# LED_Driver_and_Switches.net
KiCad netlist of a schematic drawn in Altium Designer
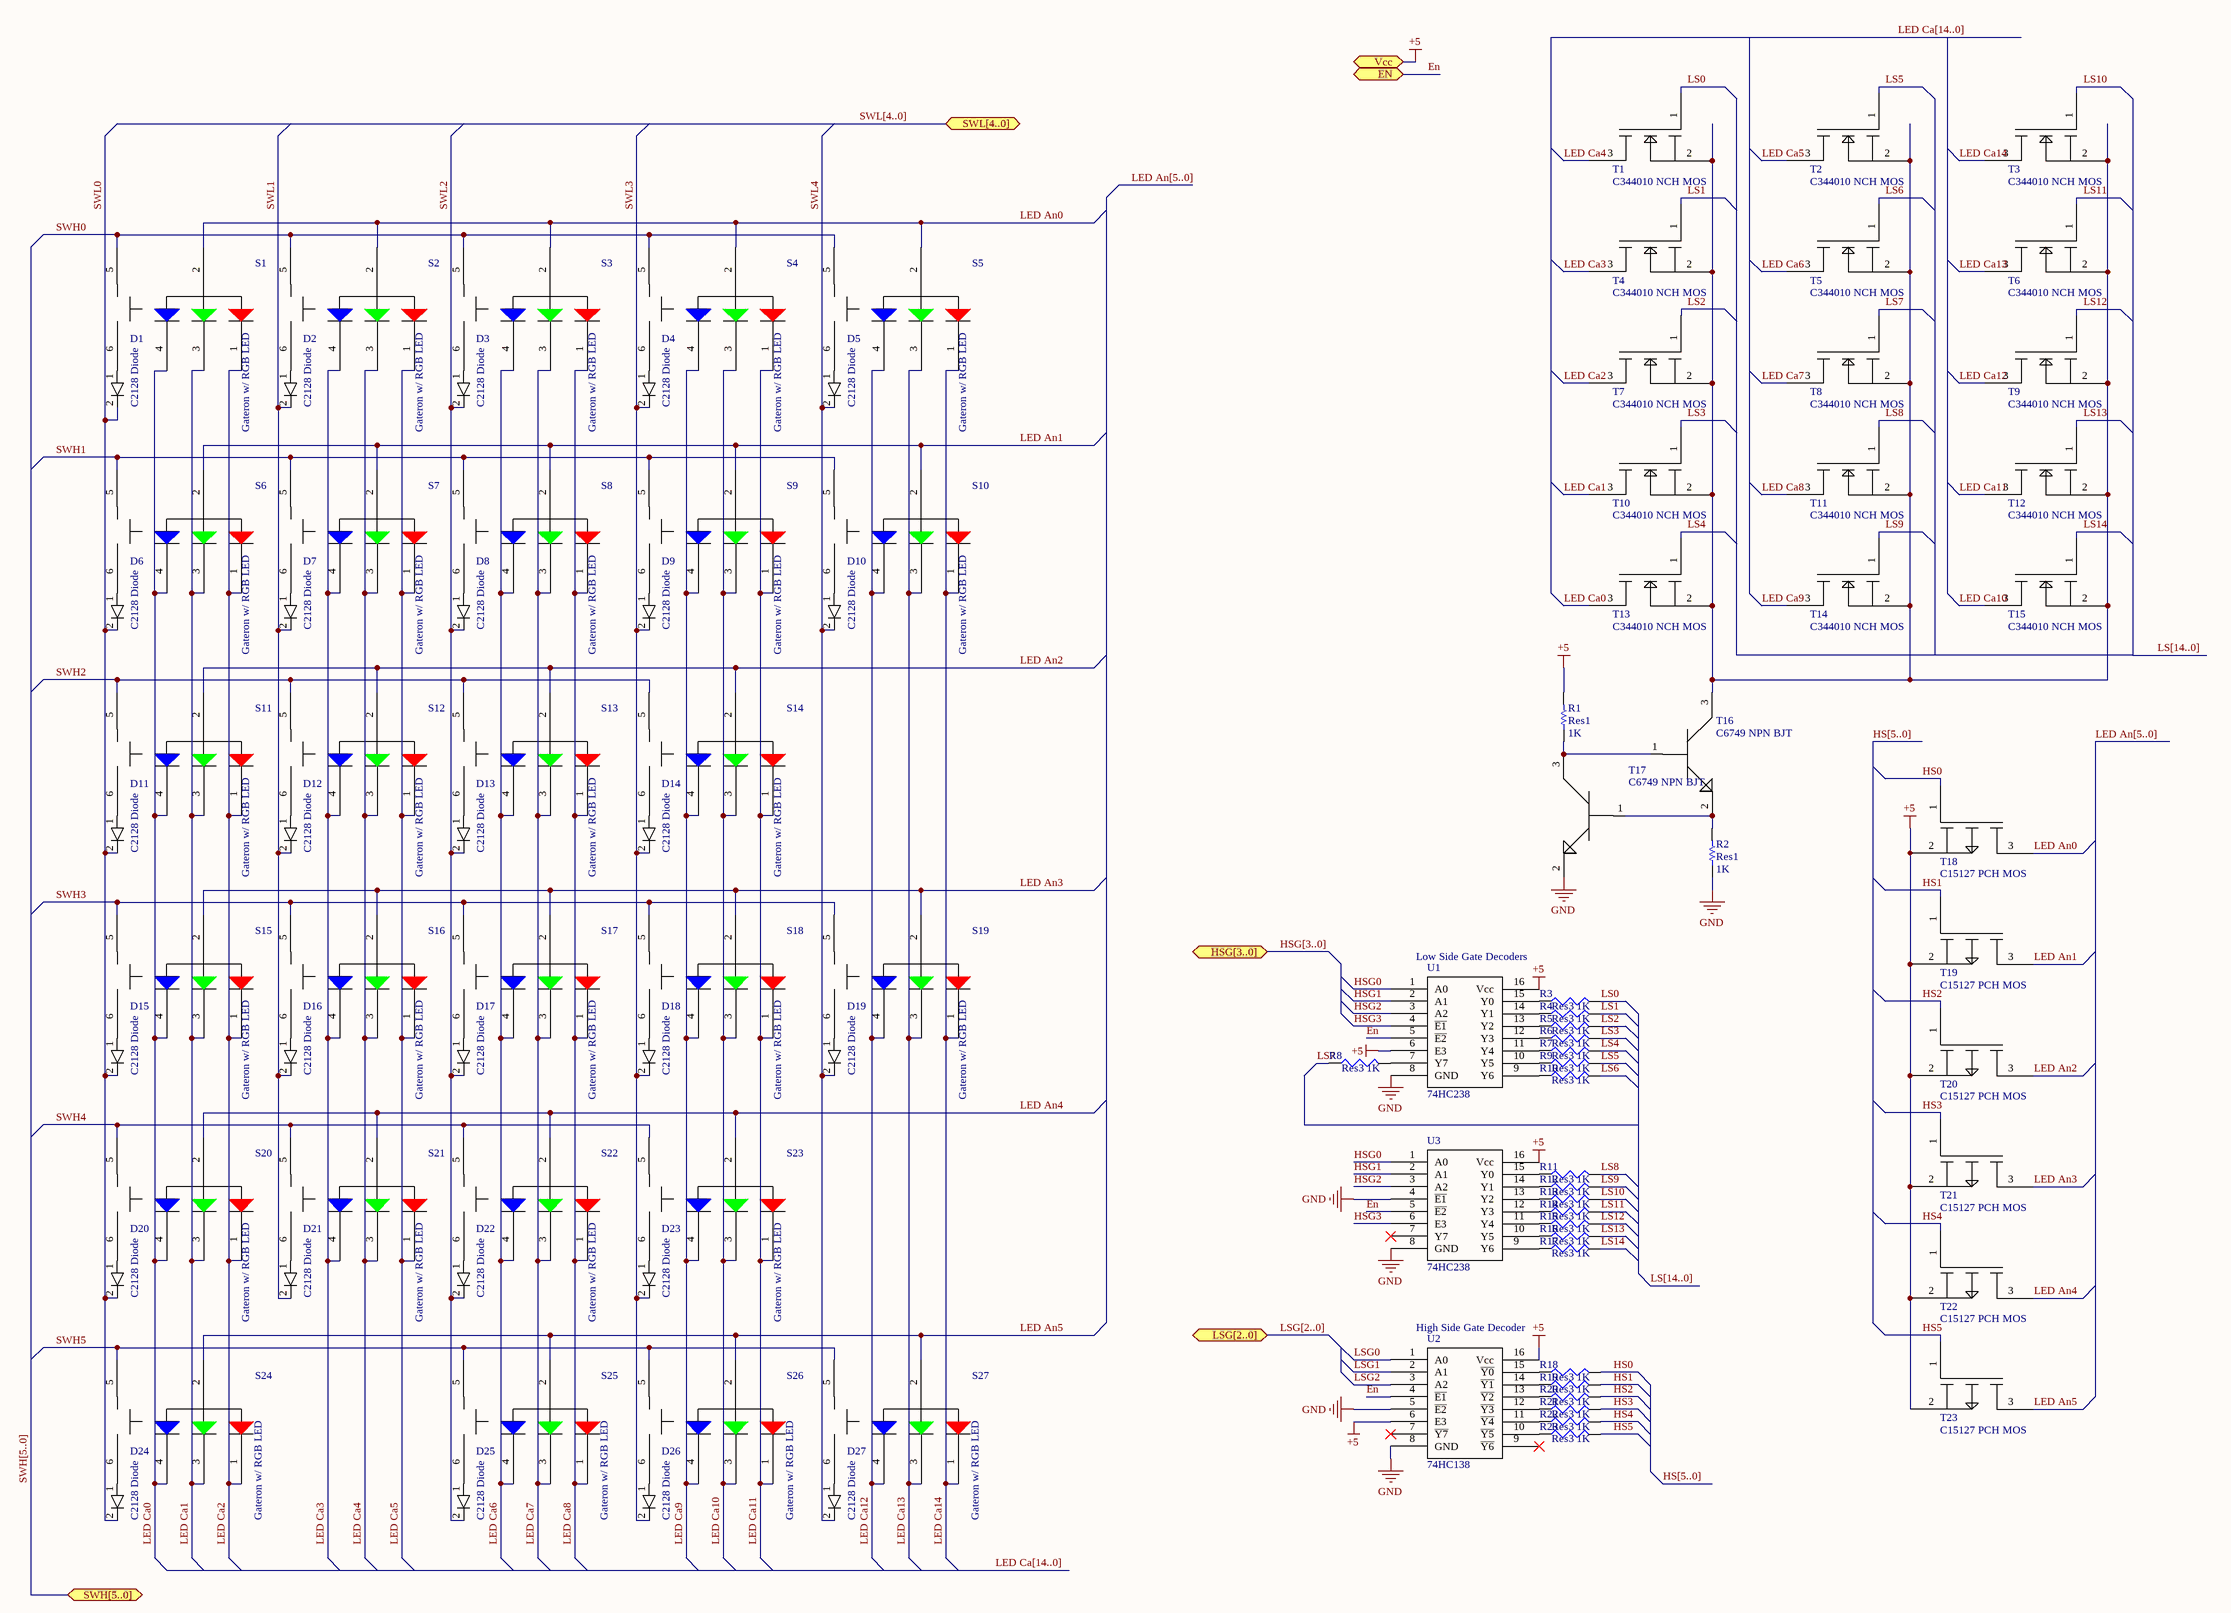
[diagram p0: LED Driver and Switches.SchDoc]

(export (version "E")
  (design (tool "Eeschema 10.0.6"))
  (components
    (comp (ref "D1")
      (value "C2128 Diode")
      (footprint "C2128 SOD323")
      (libsource (lib "2020-09-26_17-27-19") (part "C2128 Diode"))
    )
    (comp (ref "D2")
      (value "C2128 Diode")
      (footprint "C2128 SOD323")
      (libsource (lib "2020-09-26_17-27-19") (part "C2128 Diode"))
    )
    (comp (ref "D3")
      (value "C2128 Diode")
      (footprint "C2128 SOD323")
      (libsource (lib "2020-09-26_17-27-19") (part "C2128 Diode"))
    )
    (comp (ref "D4")
      (value "C2128 Diode")
      (footprint "C2128 SOD323")
      (libsource (lib "2020-09-26_17-27-19") (part "C2128 Diode"))
    )
    (comp (ref "D5")
      (value "C2128 Diode")
      (footprint "C2128 SOD323")
      (libsource (lib "2020-09-26_17-27-19") (part "C2128 Diode"))
    )
    (comp (ref "D6")
      (value "C2128 Diode")
      (footprint "C2128 SOD323")
      (libsource (lib "2020-09-26_17-27-19") (part "C2128 Diode"))
    )
    (comp (ref "D7")
      (value "C2128 Diode")
      (footprint "C2128 SOD323")
      (libsource (lib "2020-09-26_17-27-19") (part "C2128 Diode"))
    )
    (comp (ref "D8")
      (value "C2128 Diode")
      (footprint "C2128 SOD323")
      (libsource (lib "2020-09-26_17-27-19") (part "C2128 Diode"))
    )
    (comp (ref "D9")
      (value "C2128 Diode")
      (footprint "C2128 SOD323")
      (libsource (lib "2020-09-26_17-27-19") (part "C2128 Diode"))
    )
    (comp (ref "D10")
      (value "C2128 Diode")
      (footprint "C2128 SOD323")
      (libsource (lib "2020-09-26_17-27-19") (part "C2128 Diode"))
    )
    (comp (ref "D11")
      (value "C2128 Diode")
      (footprint "C2128 SOD323")
      (libsource (lib "2020-09-26_17-27-19") (part "C2128 Diode"))
    )
    (comp (ref "D12")
      (value "C2128 Diode")
      (footprint "C2128 SOD323")
      (libsource (lib "2020-09-26_17-27-19") (part "C2128 Diode"))
    )
    (comp (ref "D13")
      (value "C2128 Diode")
      (footprint "C2128 SOD323")
      (libsource (lib "2020-09-26_17-27-19") (part "C2128 Diode"))
    )
    (comp (ref "D14")
      (value "C2128 Diode")
      (footprint "C2128 SOD323")
      (libsource (lib "2020-09-26_17-27-19") (part "C2128 Diode"))
    )
    (comp (ref "D15")
      (value "C2128 Diode")
      (footprint "C2128 SOD323")
      (libsource (lib "2020-09-26_17-27-19") (part "C2128 Diode"))
    )
    (comp (ref "D16")
      (value "C2128 Diode")
      (footprint "C2128 SOD323")
      (libsource (lib "2020-09-26_17-27-19") (part "C2128 Diode"))
    )
    (comp (ref "D17")
      (value "C2128 Diode")
      (footprint "C2128 SOD323")
      (libsource (lib "2020-09-26_17-27-19") (part "C2128 Diode"))
    )
    (comp (ref "D18")
      (value "C2128 Diode")
      (footprint "C2128 SOD323")
      (libsource (lib "2020-09-26_17-27-19") (part "C2128 Diode"))
    )
    (comp (ref "D19")
      (value "C2128 Diode")
      (footprint "C2128 SOD323")
      (libsource (lib "2020-09-26_17-27-19") (part "C2128 Diode"))
    )
    (comp (ref "D20")
      (value "C2128 Diode")
      (footprint "C2128 SOD323")
      (libsource (lib "2020-09-26_17-27-19") (part "C2128 Diode"))
    )
    (comp (ref "D21")
      (value "C2128 Diode")
      (footprint "C2128 SOD323")
      (libsource (lib "2020-09-26_17-27-19") (part "C2128 Diode"))
    )
    (comp (ref "D22")
      (value "C2128 Diode")
      (footprint "C2128 SOD323")
      (libsource (lib "2020-09-26_17-27-19") (part "C2128 Diode"))
    )
    (comp (ref "D23")
      (value "C2128 Diode")
      (footprint "C2128 SOD323")
      (libsource (lib "2020-09-26_17-27-19") (part "C2128 Diode"))
    )
    (comp (ref "D24")
      (value "C2128 Diode")
      (footprint "C2128 SOD323")
      (libsource (lib "2020-09-26_17-27-19") (part "C2128 Diode"))
    )
    (comp (ref "D25")
      (value "C2128 Diode")
      (footprint "C2128 SOD323")
      (libsource (lib "2020-09-26_17-27-19") (part "C2128 Diode"))
    )
    (comp (ref "D26")
      (value "C2128 Diode")
      (footprint "C2128 SOD323")
      (libsource (lib "2020-09-26_17-27-19") (part "C2128 Diode"))
    )
    (comp (ref "D27")
      (value "C2128 Diode")
      (footprint "C2128 SOD323")
      (libsource (lib "2020-09-26_17-27-19") (part "C2128 Diode"))
    )
    (comp (ref "R1")
      (value "Res1")
      (footprint "AXIAL-0.3")
      (description "Resistor")
      (fields (field (name "ALTIUM_VALUE") "1K") (field (name "PUBLISHER") "Altium Limited"))
      (libsource (lib "Miscellaneous Devices") (part "Res1"))
    )
    (comp (ref "R2")
      (value "Res1")
      (footprint "AXIAL-0.3")
      (description "Resistor")
      (fields (field (name "ALTIUM_VALUE") "1K") (field (name "PUBLISHER") "Altium Limited"))
      (libsource (lib "Miscellaneous Devices") (part "Res1"))
    )
    (comp (ref "R3")
      (value "Res3")
      (footprint "J1-0603")
      (description "Resistor")
      (fields (field (name "ALTIUM_VALUE") "1K") (field (name "PUBLISHER") "Altium Limited"))
      (libsource (lib "Miscellaneous Devices") (part "Res3"))
    )
    (comp (ref "R4")
      (value "Res3")
      (footprint "J1-0603")
      (description "Resistor")
      (fields (field (name "ALTIUM_VALUE") "1K") (field (name "PUBLISHER") "Altium Limited"))
      (libsource (lib "Miscellaneous Devices") (part "Res3"))
    )
    (comp (ref "R5")
      (value "Res3")
      (footprint "J1-0603")
      (description "Resistor")
      (fields (field (name "ALTIUM_VALUE") "1K") (field (name "PUBLISHER") "Altium Limited"))
      (libsource (lib "Miscellaneous Devices") (part "Res3"))
    )
    (comp (ref "R6")
      (value "Res3")
      (footprint "J1-0603")
      (description "Resistor")
      (fields (field (name "ALTIUM_VALUE") "1K") (field (name "PUBLISHER") "Altium Limited"))
      (libsource (lib "Miscellaneous Devices") (part "Res3"))
    )
    (comp (ref "R7")
      (value "Res3")
      (footprint "J1-0603")
      (description "Resistor")
      (fields (field (name "ALTIUM_VALUE") "1K") (field (name "PUBLISHER") "Altium Limited"))
      (libsource (lib "Miscellaneous Devices") (part "Res3"))
    )
    (comp (ref "R8")
      (value "Res3")
      (footprint "J1-0603")
      (description "Resistor")
      (fields (field (name "ALTIUM_VALUE") "1K") (field (name "PUBLISHER") "Altium Limited"))
      (libsource (lib "Miscellaneous Devices") (part "Res3"))
    )
    (comp (ref "R9")
      (value "Res3")
      (footprint "J1-0603")
      (description "Resistor")
      (fields (field (name "ALTIUM_VALUE") "1K") (field (name "PUBLISHER") "Altium Limited"))
      (libsource (lib "Miscellaneous Devices") (part "Res3"))
    )
    (comp (ref "R10")
      (value "Res3")
      (footprint "J1-0603")
      (description "Resistor")
      (fields (field (name "ALTIUM_VALUE") "1K") (field (name "PUBLISHER") "Altium Limited"))
      (libsource (lib "Miscellaneous Devices") (part "Res3"))
    )
    (comp (ref "R11")
      (value "Res3")
      (footprint "J1-0603")
      (description "Resistor")
      (fields (field (name "ALTIUM_VALUE") "1K") (field (name "PUBLISHER") "Altium Limited"))
      (libsource (lib "Miscellaneous Devices") (part "Res3"))
    )
    (comp (ref "R12")
      (value "Res3")
      (footprint "J1-0603")
      (description "Resistor")
      (fields (field (name "ALTIUM_VALUE") "1K") (field (name "PUBLISHER") "Altium Limited"))
      (libsource (lib "Miscellaneous Devices") (part "Res3"))
    )
    (comp (ref "R13")
      (value "Res3")
      (footprint "J1-0603")
      (description "Resistor")
      (fields (field (name "ALTIUM_VALUE") "1K") (field (name "PUBLISHER") "Altium Limited"))
      (libsource (lib "Miscellaneous Devices") (part "Res3"))
    )
    (comp (ref "R14")
      (value "Res3")
      (footprint "J1-0603")
      (description "Resistor")
      (fields (field (name "ALTIUM_VALUE") "1K") (field (name "PUBLISHER") "Altium Limited"))
      (libsource (lib "Miscellaneous Devices") (part "Res3"))
    )
    (comp (ref "R15")
      (value "Res3")
      (footprint "J1-0603")
      (description "Resistor")
      (fields (field (name "ALTIUM_VALUE") "1K") (field (name "PUBLISHER") "Altium Limited"))
      (libsource (lib "Miscellaneous Devices") (part "Res3"))
    )
    (comp (ref "R16")
      (value "Res3")
      (footprint "J1-0603")
      (description "Resistor")
      (fields (field (name "ALTIUM_VALUE") "1K") (field (name "PUBLISHER") "Altium Limited"))
      (libsource (lib "Miscellaneous Devices") (part "Res3"))
    )
    (comp (ref "R17")
      (value "Res3")
      (footprint "J1-0603")
      (description "Resistor")
      (fields (field (name "ALTIUM_VALUE") "1K") (field (name "PUBLISHER") "Altium Limited"))
      (libsource (lib "Miscellaneous Devices") (part "Res3"))
    )
    (comp (ref "R18")
      (value "Res3")
      (footprint "J1-0603")
      (description "Resistor")
      (fields (field (name "ALTIUM_VALUE") "1K") (field (name "PUBLISHER") "Altium Limited"))
      (libsource (lib "Miscellaneous Devices") (part "Res3"))
    )
    (comp (ref "R19")
      (value "Res3")
      (footprint "J1-0603")
      (description "Resistor")
      (fields (field (name "ALTIUM_VALUE") "1K") (field (name "PUBLISHER") "Altium Limited"))
      (libsource (lib "Miscellaneous Devices") (part "Res3"))
    )
    (comp (ref "R20")
      (value "Res3")
      (footprint "J1-0603")
      (description "Resistor")
      (fields (field (name "ALTIUM_VALUE") "1K") (field (name "PUBLISHER") "Altium Limited"))
      (libsource (lib "Miscellaneous Devices") (part "Res3"))
    )
    (comp (ref "R21")
      (value "Res3")
      (footprint "J1-0603")
      (description "Resistor")
      (fields (field (name "ALTIUM_VALUE") "1K") (field (name "PUBLISHER") "Altium Limited"))
      (libsource (lib "Miscellaneous Devices") (part "Res3"))
    )
    (comp (ref "R22")
      (value "Res3")
      (footprint "J1-0603")
      (description "Resistor")
      (fields (field (name "ALTIUM_VALUE") "1K") (field (name "PUBLISHER") "Altium Limited"))
      (libsource (lib "Miscellaneous Devices") (part "Res3"))
    )
    (comp (ref "R23")
      (value "Res3")
      (footprint "J1-0603")
      (description "Resistor")
      (fields (field (name "ALTIUM_VALUE") "1K") (field (name "PUBLISHER") "Altium Limited"))
      (libsource (lib "Miscellaneous Devices") (part "Res3"))
    )
    (comp (ref "S1")
      (value "Gateron w/ RGB LED")
      (footprint "Gateron Green")
      (libsource (lib "2020-09-26_17-27-19") (part "Gateron Green"))
    )
    (comp (ref "S2")
      (value "Gateron w/ RGB LED")
      (footprint "Gateron Green")
      (libsource (lib "2020-09-26_17-27-19") (part "Gateron Green"))
    )
    (comp (ref "S3")
      (value "Gateron w/ RGB LED")
      (footprint "Gateron Green")
      (libsource (lib "2020-09-26_17-27-19") (part "Gateron Green"))
    )
    (comp (ref "S4")
      (value "Gateron w/ RGB LED")
      (footprint "Gateron Green")
      (libsource (lib "2020-09-26_17-27-19") (part "Gateron Green"))
    )
    (comp (ref "S5")
      (value "Gateron w/ RGB LED")
      (footprint "Gateron Green")
      (libsource (lib "2020-09-26_17-27-19") (part "Gateron Green"))
    )
    (comp (ref "S6")
      (value "Gateron w/ RGB LED")
      (footprint "Gateron Green")
      (libsource (lib "2020-09-26_17-27-19") (part "Gateron Green"))
    )
    (comp (ref "S7")
      (value "Gateron w/ RGB LED")
      (footprint "Gateron Green")
      (libsource (lib "2020-09-26_17-27-19") (part "Gateron Green"))
    )
    (comp (ref "S8")
      (value "Gateron w/ RGB LED")
      (footprint "Gateron Green")
      (libsource (lib "2020-09-26_17-27-19") (part "Gateron Green"))
    )
    (comp (ref "S9")
      (value "Gateron w/ RGB LED")
      (footprint "Gateron Green")
      (libsource (lib "2020-09-26_17-27-19") (part "Gateron Green"))
    )
    (comp (ref "S10")
      (value "Gateron w/ RGB LED")
      (footprint "Gateron Green")
      (libsource (lib "2020-09-26_17-27-19") (part "Gateron Green"))
    )
    (comp (ref "S11")
      (value "Gateron w/ RGB LED")
      (footprint "Gateron Green")
      (libsource (lib "2020-09-26_17-27-19") (part "Gateron Green"))
    )
    (comp (ref "S12")
      (value "Gateron w/ RGB LED")
      (footprint "Gateron Green")
      (libsource (lib "2020-09-26_17-27-19") (part "Gateron Green"))
    )
    (comp (ref "S13")
      (value "Gateron w/ RGB LED")
      (footprint "Gateron Green")
      (libsource (lib "2020-09-26_17-27-19") (part "Gateron Green"))
    )
    (comp (ref "S14")
      (value "Gateron w/ RGB LED")
      (footprint "Gateron Green")
      (libsource (lib "2020-09-26_17-27-19") (part "Gateron Green"))
    )
    (comp (ref "S15")
      (value "Gateron w/ RGB LED")
      (footprint "Gateron Green")
      (libsource (lib "2020-09-26_17-27-19") (part "Gateron Green"))
    )
    (comp (ref "S16")
      (value "Gateron w/ RGB LED")
      (footprint "Gateron Green")
      (libsource (lib "2020-09-26_17-27-19") (part "Gateron Green"))
    )
    (comp (ref "S17")
      (value "Gateron w/ RGB LED")
      (footprint "Gateron Green")
      (libsource (lib "2020-09-26_17-27-19") (part "Gateron Green"))
    )
    (comp (ref "S18")
      (value "Gateron w/ RGB LED")
      (footprint "Gateron Green")
      (libsource (lib "2020-09-26_17-27-19") (part "Gateron Green"))
    )
    (comp (ref "S19")
      (value "Gateron w/ RGB LED")
      (footprint "Gateron Green")
      (libsource (lib "2020-09-26_17-27-19") (part "Gateron Green"))
    )
    (comp (ref "S20")
      (value "Gateron w/ RGB LED")
      (footprint "Gateron Green")
      (libsource (lib "2020-09-26_17-27-19") (part "Gateron Green"))
    )
    (comp (ref "S21")
      (value "Gateron w/ RGB LED")
      (footprint "Gateron Green")
      (libsource (lib "2020-09-26_17-27-19") (part "Gateron Green"))
    )
    (comp (ref "S22")
      (value "Gateron w/ RGB LED")
      (footprint "Gateron Green")
      (libsource (lib "2020-09-26_17-27-19") (part "Gateron Green"))
    )
    (comp (ref "S23")
      (value "Gateron w/ RGB LED")
      (footprint "Gateron Green")
      (libsource (lib "2020-09-26_17-27-19") (part "Gateron Green"))
    )
    (comp (ref "S24")
      (value "Gateron w/ RGB LED")
      (footprint "Gateron Green")
      (libsource (lib "2020-09-26_17-27-19") (part "Gateron Green"))
    )
    (comp (ref "S25")
      (value "Gateron w/ RGB LED")
      (footprint "Gateron Green")
      (libsource (lib "2020-09-26_17-27-19") (part "Gateron Green"))
    )
    (comp (ref "S26")
      (value "Gateron w/ RGB LED")
      (footprint "Gateron Green")
      (libsource (lib "2020-09-26_17-27-19") (part "Gateron Green"))
    )
    (comp (ref "S27")
      (value "Gateron w/ RGB LED")
      (footprint "Gateron Green")
      (libsource (lib "2020-09-26_17-27-19") (part "Gateron Green"))
    )
    (comp (ref "T1")
      (value "C344010 NCH MOS")
      (footprint "C6749 NPN BJT")
      (libsource (lib "2020-09-26_17-27-19") (part "C344010 NCH MOS"))
    )
    (comp (ref "T2")
      (value "C344010 NCH MOS")
      (footprint "C6749 NPN BJT")
      (libsource (lib "2020-09-26_17-27-19") (part "C344010 NCH MOS"))
    )
    (comp (ref "T3")
      (value "C344010 NCH MOS")
      (footprint "C6749 NPN BJT")
      (libsource (lib "2020-09-26_17-27-19") (part "C344010 NCH MOS"))
    )
    (comp (ref "T4")
      (value "C344010 NCH MOS")
      (footprint "C6749 NPN BJT")
      (libsource (lib "2020-09-26_17-27-19") (part "C344010 NCH MOS"))
    )
    (comp (ref "T5")
      (value "C344010 NCH MOS")
      (footprint "C6749 NPN BJT")
      (libsource (lib "2020-09-26_17-27-19") (part "C344010 NCH MOS"))
    )
    (comp (ref "T6")
      (value "C344010 NCH MOS")
      (footprint "C6749 NPN BJT")
      (libsource (lib "2020-09-26_17-27-19") (part "C344010 NCH MOS"))
    )
    (comp (ref "T7")
      (value "C344010 NCH MOS")
      (footprint "C6749 NPN BJT")
      (libsource (lib "2020-09-26_17-27-19") (part "C344010 NCH MOS"))
    )
    (comp (ref "T8")
      (value "C344010 NCH MOS")
      (footprint "C6749 NPN BJT")
      (libsource (lib "2020-09-26_17-27-19") (part "C344010 NCH MOS"))
    )
    (comp (ref "T9")
      (value "C344010 NCH MOS")
      (footprint "C6749 NPN BJT")
      (libsource (lib "2020-09-26_17-27-19") (part "C344010 NCH MOS"))
    )
    (comp (ref "T10")
      (value "C344010 NCH MOS")
      (footprint "C6749 NPN BJT")
      (libsource (lib "2020-09-26_17-27-19") (part "C344010 NCH MOS"))
    )
    (comp (ref "T11")
      (value "C344010 NCH MOS")
      (footprint "C6749 NPN BJT")
      (libsource (lib "2020-09-26_17-27-19") (part "C344010 NCH MOS"))
    )
    (comp (ref "T12")
      (value "C344010 NCH MOS")
      (footprint "C6749 NPN BJT")
      (libsource (lib "2020-09-26_17-27-19") (part "C344010 NCH MOS"))
    )
    (comp (ref "T13")
      (value "C344010 NCH MOS")
      (footprint "C6749 NPN BJT")
      (libsource (lib "2020-09-26_17-27-19") (part "C344010 NCH MOS"))
    )
    (comp (ref "T14")
      (value "C344010 NCH MOS")
      (footprint "C6749 NPN BJT")
      (libsource (lib "2020-09-26_17-27-19") (part "C344010 NCH MOS"))
    )
    (comp (ref "T15")
      (value "C344010 NCH MOS")
      (footprint "C6749 NPN BJT")
      (libsource (lib "2020-09-26_17-27-19") (part "C344010 NCH MOS"))
    )
    (comp (ref "T16")
      (value "C6749 NPN BJT")
      (footprint "C6749 NPN BJT")
      (libsource (lib "2020-09-26_17-27-19") (part "C6749 NPN BJT"))
    )
    (comp (ref "T17")
      (value "C6749 NPN BJT")
      (footprint "C6749 NPN BJT")
      (libsource (lib "2020-09-26_17-27-19") (part "C6749 NPN BJT"))
    )
    (comp (ref "T18")
      (value "C15127 PCH MOS")
      (footprint "C6749 NPN BJT")
      (libsource (lib "2020-09-26_17-27-19") (part "C15127 PCH MOS"))
    )
    (comp (ref "T19")
      (value "C15127 PCH MOS")
      (footprint "C6749 NPN BJT")
      (libsource (lib "2020-09-26_17-27-19") (part "C15127 PCH MOS"))
    )
    (comp (ref "T20")
      (value "C15127 PCH MOS")
      (footprint "C6749 NPN BJT")
      (libsource (lib "2020-09-26_17-27-19") (part "C15127 PCH MOS"))
    )
    (comp (ref "T21")
      (value "C15127 PCH MOS")
      (footprint "C6749 NPN BJT")
      (libsource (lib "2020-09-26_17-27-19") (part "C15127 PCH MOS"))
    )
    (comp (ref "T22")
      (value "C15127 PCH MOS")
      (footprint "C6749 NPN BJT")
      (libsource (lib "2020-09-26_17-27-19") (part "C15127 PCH MOS"))
    )
    (comp (ref "T23")
      (value "C15127 PCH MOS")
      (footprint "C6749 NPN BJT")
      (libsource (lib "2020-09-26_17-27-19") (part "C15127 PCH MOS"))
    )
    (comp (ref "U1")
      (value "74HC238")
      (footprint "SOIC16")
      (libsource (lib "2020-09-26_17-27-19") (part "74HC238"))
    )
    (comp (ref "U2")
      (value "74HC138")
      (footprint "SOIC16")
      (libsource (lib "2020-09-26_17-27-19") (part "74HC138"))
    )
    (comp (ref "U3")
      (value "74HC238")
      (footprint "SOIC16")
      (libsource (lib "2020-09-26_17-27-19") (part "74HC238"))
    )
  )
  (nets
    (net (code "1") (name "+5") (class "Default")
      (node (ref "R1") (pin "2") (pinfunction "2_2") (pintype "passive"))
      (node (ref "T18") (pin "2") (pintype "passive"))
      (node (ref "T19") (pin "2") (pintype "passive"))
      (node (ref "T20") (pin "2") (pintype "passive"))
      (node (ref "T21") (pin "2") (pintype "passive"))
      (node (ref "T22") (pin "2") (pintype "passive"))
      (node (ref "T23") (pin "2") (pintype "passive"))
      (node (ref "U1") (pin "16") (pinfunction "Vcc_16") (pintype "passive"))
      (node (ref "U1") (pin "6") (pinfunction "E3_6") (pintype "passive"))
      (node (ref "U2") (pin "16") (pinfunction "Vcc_16") (pintype "passive"))
      (node (ref "U2") (pin "6") (pinfunction "E3_6") (pintype "passive"))
      (node (ref "U3") (pin "16") (pinfunction "Vcc_16") (pintype "passive"))
    )
    (net (code "2") (name "/En") (class "Default")
      (node (ref "U1") (pin "5") (pinfunction "~{E2}_5") (pintype "passive"))
      (node (ref "U2") (pin "4") (pinfunction "~{E1}_4") (pintype "passive"))
      (node (ref "U3") (pin "5") (pinfunction "~{E2}_5") (pintype "passive"))
    )
    (net (code "3") (name "/HS0") (class "Default")
      (node (ref "R18") (pin "2") (pinfunction "2_2") (pintype "passive"))
      (node (ref "T18") (pin "1") (pintype "passive"))
    )
    (net (code "4") (name "/HS1") (class "Default")
      (node (ref "R19") (pin "2") (pinfunction "2_2") (pintype "passive"))
      (node (ref "T19") (pin "1") (pintype "passive"))
    )
    (net (code "5") (name "/HS2") (class "Default")
      (node (ref "R20") (pin "2") (pinfunction "2_2") (pintype "passive"))
      (node (ref "T20") (pin "1") (pintype "passive"))
    )
    (net (code "6") (name "/HS3") (class "Default")
      (node (ref "R21") (pin "2") (pinfunction "2_2") (pintype "passive"))
      (node (ref "T21") (pin "1") (pintype "passive"))
    )
    (net (code "7") (name "/HS4") (class "Default")
      (node (ref "R22") (pin "2") (pinfunction "2_2") (pintype "passive"))
      (node (ref "T22") (pin "1") (pintype "passive"))
    )
    (net (code "8") (name "/HS5") (class "Default")
      (node (ref "R23") (pin "2") (pinfunction "2_2") (pintype "passive"))
      (node (ref "T23") (pin "1") (pintype "passive"))
    )
    (net (code "9") (name "/HSG0") (class "Default")
      (node (ref "U1") (pin "1") (pinfunction "A0_1") (pintype "passive"))
      (node (ref "U3") (pin "1") (pinfunction "A0_1") (pintype "passive"))
    )
    (net (code "10") (name "/HSG1") (class "Default")
      (node (ref "U1") (pin "2") (pinfunction "A1_2") (pintype "passive"))
      (node (ref "U3") (pin "2") (pinfunction "A1_2") (pintype "passive"))
    )
    (net (code "11") (name "/HSG2") (class "Default")
      (node (ref "U1") (pin "3") (pinfunction "A2_3") (pintype "passive"))
      (node (ref "U3") (pin "3") (pinfunction "A2_3") (pintype "passive"))
    )
    (net (code "12") (name "/HSG3") (class "Default")
      (node (ref "U1") (pin "4") (pinfunction "~{E1}_4") (pintype "passive"))
      (node (ref "U3") (pin "6") (pinfunction "E3_6") (pintype "passive"))
    )
    (net (code "15") (name "/LED An0") (class "Default")
      (node (ref "S1") (pin "2") (pinfunction "COM_2") (pintype "passive"))
      (node (ref "S2") (pin "2") (pinfunction "COM_2") (pintype "passive"))
      (node (ref "S3") (pin "2") (pinfunction "COM_2") (pintype "passive"))
      (node (ref "S4") (pin "2") (pinfunction "COM_2") (pintype "passive"))
      (node (ref "S5") (pin "2") (pinfunction "COM_2") (pintype "passive"))
      (node (ref "T18") (pin "3") (pintype "passive"))
    )
    (net (code "16") (name "/LED An1") (class "Default")
      (node (ref "S10") (pin "2") (pinfunction "COM_2") (pintype "passive"))
      (node (ref "S6") (pin "2") (pinfunction "COM_2") (pintype "passive"))
      (node (ref "S7") (pin "2") (pinfunction "COM_2") (pintype "passive"))
      (node (ref "S8") (pin "2") (pinfunction "COM_2") (pintype "passive"))
      (node (ref "S9") (pin "2") (pinfunction "COM_2") (pintype "passive"))
      (node (ref "T19") (pin "3") (pintype "passive"))
    )
    (net (code "17") (name "/LED An2") (class "Default")
      (node (ref "S11") (pin "2") (pinfunction "COM_2") (pintype "passive"))
      (node (ref "S12") (pin "2") (pinfunction "COM_2") (pintype "passive"))
      (node (ref "S13") (pin "2") (pinfunction "COM_2") (pintype "passive"))
      (node (ref "S14") (pin "2") (pinfunction "COM_2") (pintype "passive"))
      (node (ref "T20") (pin "3") (pintype "passive"))
    )
    (net (code "18") (name "/LED An3") (class "Default")
      (node (ref "S15") (pin "2") (pinfunction "COM_2") (pintype "passive"))
      (node (ref "S16") (pin "2") (pinfunction "COM_2") (pintype "passive"))
      (node (ref "S17") (pin "2") (pinfunction "COM_2") (pintype "passive"))
      (node (ref "S18") (pin "2") (pinfunction "COM_2") (pintype "passive"))
      (node (ref "S19") (pin "2") (pinfunction "COM_2") (pintype "passive"))
      (node (ref "T21") (pin "3") (pintype "passive"))
    )
    (net (code "19") (name "/LED An4") (class "Default")
      (node (ref "S20") (pin "2") (pinfunction "COM_2") (pintype "passive"))
      (node (ref "S21") (pin "2") (pinfunction "COM_2") (pintype "passive"))
      (node (ref "S22") (pin "2") (pinfunction "COM_2") (pintype "passive"))
      (node (ref "S23") (pin "2") (pinfunction "COM_2") (pintype "passive"))
      (node (ref "T22") (pin "3") (pintype "passive"))
    )
    (net (code "20") (name "/LED An5") (class "Default")
      (node (ref "S24") (pin "2") (pinfunction "COM_2") (pintype "passive"))
      (node (ref "S25") (pin "2") (pinfunction "COM_2") (pintype "passive"))
      (node (ref "S26") (pin "2") (pinfunction "COM_2") (pintype "passive"))
      (node (ref "S27") (pin "2") (pinfunction "COM_2") (pintype "passive"))
      (node (ref "T23") (pin "3") (pintype "passive"))
    )
    (net (code "21") (name "/LED Ca0") (class "Default")
      (node (ref "S1") (pin "4") (pinfunction "B_4") (pintype "passive"))
      (node (ref "S11") (pin "4") (pinfunction "B_4") (pintype "passive"))
      (node (ref "S15") (pin "4") (pinfunction "B_4") (pintype "passive"))
      (node (ref "S20") (pin "4") (pinfunction "B_4") (pintype "passive"))
      (node (ref "S24") (pin "4") (pinfunction "B_4") (pintype "passive"))
      (node (ref "S6") (pin "4") (pinfunction "B_4") (pintype "passive"))
      (node (ref "T13") (pin "3") (pintype "passive"))
    )
    (net (code "22") (name "/LED Ca1") (class "Default")
      (node (ref "S1") (pin "3") (pinfunction "G_3") (pintype "passive"))
      (node (ref "S11") (pin "3") (pinfunction "G_3") (pintype "passive"))
      (node (ref "S15") (pin "3") (pinfunction "G_3") (pintype "passive"))
      (node (ref "S20") (pin "3") (pinfunction "G_3") (pintype "passive"))
      (node (ref "S24") (pin "3") (pinfunction "G_3") (pintype "passive"))
      (node (ref "S6") (pin "3") (pinfunction "G_3") (pintype "passive"))
      (node (ref "T10") (pin "3") (pintype "passive"))
    )
    (net (code "23") (name "/LED Ca2") (class "Default")
      (node (ref "S1") (pin "1") (pinfunction "R_1") (pintype "passive"))
      (node (ref "S11") (pin "1") (pinfunction "R_1") (pintype "passive"))
      (node (ref "S15") (pin "1") (pinfunction "R_1") (pintype "passive"))
      (node (ref "S20") (pin "1") (pinfunction "R_1") (pintype "passive"))
      (node (ref "S24") (pin "1") (pinfunction "R_1") (pintype "passive"))
      (node (ref "S6") (pin "1") (pinfunction "R_1") (pintype "passive"))
      (node (ref "T7") (pin "3") (pintype "passive"))
    )
    (net (code "24") (name "/LED Ca3") (class "Default")
      (node (ref "S12") (pin "4") (pinfunction "B_4") (pintype "passive"))
      (node (ref "S16") (pin "4") (pinfunction "B_4") (pintype "passive"))
      (node (ref "S2") (pin "4") (pinfunction "B_4") (pintype "passive"))
      (node (ref "S21") (pin "4") (pinfunction "B_4") (pintype "passive"))
      (node (ref "S7") (pin "4") (pinfunction "B_4") (pintype "passive"))
      (node (ref "T4") (pin "3") (pintype "passive"))
    )
    (net (code "25") (name "/LED Ca4") (class "Default")
      (node (ref "S12") (pin "3") (pinfunction "G_3") (pintype "passive"))
      (node (ref "S16") (pin "3") (pinfunction "G_3") (pintype "passive"))
      (node (ref "S2") (pin "3") (pinfunction "G_3") (pintype "passive"))
      (node (ref "S21") (pin "3") (pinfunction "G_3") (pintype "passive"))
      (node (ref "S7") (pin "3") (pinfunction "G_3") (pintype "passive"))
      (node (ref "T1") (pin "3") (pintype "passive"))
    )
    (net (code "26") (name "/LED Ca5") (class "Default")
      (node (ref "S12") (pin "1") (pinfunction "R_1") (pintype "passive"))
      (node (ref "S16") (pin "1") (pinfunction "R_1") (pintype "passive"))
      (node (ref "S2") (pin "1") (pinfunction "R_1") (pintype "passive"))
      (node (ref "S21") (pin "1") (pinfunction "R_1") (pintype "passive"))
      (node (ref "S7") (pin "1") (pinfunction "R_1") (pintype "passive"))
      (node (ref "T2") (pin "3") (pintype "passive"))
    )
    (net (code "27") (name "/LED Ca6") (class "Default")
      (node (ref "S13") (pin "4") (pinfunction "B_4") (pintype "passive"))
      (node (ref "S17") (pin "4") (pinfunction "B_4") (pintype "passive"))
      (node (ref "S22") (pin "4") (pinfunction "B_4") (pintype "passive"))
      (node (ref "S25") (pin "4") (pinfunction "B_4") (pintype "passive"))
      (node (ref "S3") (pin "4") (pinfunction "B_4") (pintype "passive"))
      (node (ref "S8") (pin "4") (pinfunction "B_4") (pintype "passive"))
      (node (ref "T5") (pin "3") (pintype "passive"))
    )
    (net (code "28") (name "/LED Ca7") (class "Default")
      (node (ref "S13") (pin "3") (pinfunction "G_3") (pintype "passive"))
      (node (ref "S17") (pin "3") (pinfunction "G_3") (pintype "passive"))
      (node (ref "S22") (pin "3") (pinfunction "G_3") (pintype "passive"))
      (node (ref "S25") (pin "3") (pinfunction "G_3") (pintype "passive"))
      (node (ref "S3") (pin "3") (pinfunction "G_3") (pintype "passive"))
      (node (ref "S8") (pin "3") (pinfunction "G_3") (pintype "passive"))
      (node (ref "T8") (pin "3") (pintype "passive"))
    )
    (net (code "29") (name "/LED Ca8") (class "Default")
      (node (ref "S13") (pin "1") (pinfunction "R_1") (pintype "passive"))
      (node (ref "S17") (pin "1") (pinfunction "R_1") (pintype "passive"))
      (node (ref "S22") (pin "1") (pinfunction "R_1") (pintype "passive"))
      (node (ref "S25") (pin "1") (pinfunction "R_1") (pintype "passive"))
      (node (ref "S3") (pin "1") (pinfunction "R_1") (pintype "passive"))
      (node (ref "S8") (pin "1") (pinfunction "R_1") (pintype "passive"))
      (node (ref "T11") (pin "3") (pintype "passive"))
    )
    (net (code "30") (name "/LED Ca9") (class "Default")
      (node (ref "S14") (pin "4") (pinfunction "B_4") (pintype "passive"))
      (node (ref "S18") (pin "4") (pinfunction "B_4") (pintype "passive"))
      (node (ref "S23") (pin "4") (pinfunction "B_4") (pintype "passive"))
      (node (ref "S26") (pin "4") (pinfunction "B_4") (pintype "passive"))
      (node (ref "S4") (pin "4") (pinfunction "B_4") (pintype "passive"))
      (node (ref "S9") (pin "4") (pinfunction "B_4") (pintype "passive"))
      (node (ref "T14") (pin "3") (pintype "passive"))
    )
    (net (code "31") (name "/LED Ca10") (class "Default")
      (node (ref "S14") (pin "3") (pinfunction "G_3") (pintype "passive"))
      (node (ref "S18") (pin "3") (pinfunction "G_3") (pintype "passive"))
      (node (ref "S23") (pin "3") (pinfunction "G_3") (pintype "passive"))
      (node (ref "S26") (pin "3") (pinfunction "G_3") (pintype "passive"))
      (node (ref "S4") (pin "3") (pinfunction "G_3") (pintype "passive"))
      (node (ref "S9") (pin "3") (pinfunction "G_3") (pintype "passive"))
      (node (ref "T15") (pin "3") (pintype "passive"))
    )
    (net (code "32") (name "/LED Ca11") (class "Default")
      (node (ref "S14") (pin "1") (pinfunction "R_1") (pintype "passive"))
      (node (ref "S18") (pin "1") (pinfunction "R_1") (pintype "passive"))
      (node (ref "S23") (pin "1") (pinfunction "R_1") (pintype "passive"))
      (node (ref "S26") (pin "1") (pinfunction "R_1") (pintype "passive"))
      (node (ref "S4") (pin "1") (pinfunction "R_1") (pintype "passive"))
      (node (ref "S9") (pin "1") (pinfunction "R_1") (pintype "passive"))
      (node (ref "T12") (pin "3") (pintype "passive"))
    )
    (net (code "33") (name "/LED Ca12") (class "Default")
      (node (ref "S10") (pin "4") (pinfunction "B_4") (pintype "passive"))
      (node (ref "S19") (pin "4") (pinfunction "B_4") (pintype "passive"))
      (node (ref "S27") (pin "4") (pinfunction "B_4") (pintype "passive"))
      (node (ref "S5") (pin "4") (pinfunction "B_4") (pintype "passive"))
      (node (ref "T9") (pin "3") (pintype "passive"))
    )
    (net (code "34") (name "/LED Ca13") (class "Default")
      (node (ref "S10") (pin "3") (pinfunction "G_3") (pintype "passive"))
      (node (ref "S19") (pin "3") (pinfunction "G_3") (pintype "passive"))
      (node (ref "S27") (pin "3") (pinfunction "G_3") (pintype "passive"))
      (node (ref "S5") (pin "3") (pinfunction "G_3") (pintype "passive"))
      (node (ref "T6") (pin "3") (pintype "passive"))
    )
    (net (code "35") (name "/LED Ca14") (class "Default")
      (node (ref "S10") (pin "1") (pinfunction "R_1") (pintype "passive"))
      (node (ref "S19") (pin "1") (pinfunction "R_1") (pintype "passive"))
      (node (ref "S27") (pin "1") (pinfunction "R_1") (pintype "passive"))
      (node (ref "S5") (pin "1") (pinfunction "R_1") (pintype "passive"))
      (node (ref "T3") (pin "3") (pintype "passive"))
    )
    (net (code "36") (name "/LS0") (class "Default")
      (node (ref "R3") (pin "2") (pinfunction "2_2") (pintype "passive"))
      (node (ref "T1") (pin "1") (pintype "passive"))
    )
    (net (code "37") (name "/LS1") (class "Default")
      (node (ref "R4") (pin "2") (pinfunction "2_2") (pintype "passive"))
      (node (ref "T4") (pin "1") (pintype "passive"))
    )
    (net (code "38") (name "/LS2") (class "Default")
      (node (ref "R5") (pin "2") (pinfunction "2_2") (pintype "passive"))
      (node (ref "T7") (pin "1") (pintype "passive"))
    )
    (net (code "39") (name "/LS3") (class "Default")
      (node (ref "R6") (pin "2") (pinfunction "2_2") (pintype "passive"))
      (node (ref "T10") (pin "1") (pintype "passive"))
    )
    (net (code "40") (name "/LS4") (class "Default")
      (node (ref "R7") (pin "2") (pinfunction "2_2") (pintype "passive"))
      (node (ref "T13") (pin "1") (pintype "passive"))
    )
    (net (code "41") (name "/LS5") (class "Default")
      (node (ref "R9") (pin "2") (pinfunction "2_2") (pintype "passive"))
      (node (ref "T2") (pin "1") (pintype "passive"))
    )
    (net (code "42") (name "/LS6") (class "Default")
      (node (ref "R10") (pin "2") (pinfunction "2_2") (pintype "passive"))
      (node (ref "T5") (pin "1") (pintype "passive"))
    )
    (net (code "43") (name "/LS7") (class "Default")
      (node (ref "R8") (pin "1") (pinfunction "1_1") (pintype "passive"))
      (node (ref "T8") (pin "1") (pintype "passive"))
    )
    (net (code "44") (name "/LS8") (class "Default")
      (node (ref "R11") (pin "2") (pinfunction "2_2") (pintype "passive"))
      (node (ref "T11") (pin "1") (pintype "passive"))
    )
    (net (code "45") (name "/LS9") (class "Default")
      (node (ref "R12") (pin "2") (pinfunction "2_2") (pintype "passive"))
      (node (ref "T14") (pin "1") (pintype "passive"))
    )
    (net (code "46") (name "/LS10") (class "Default")
      (node (ref "R13") (pin "2") (pinfunction "2_2") (pintype "passive"))
      (node (ref "T3") (pin "1") (pintype "passive"))
    )
    (net (code "47") (name "/LS11") (class "Default")
      (node (ref "R14") (pin "2") (pinfunction "2_2") (pintype "passive"))
      (node (ref "T6") (pin "1") (pintype "passive"))
    )
    (net (code "48") (name "/LS12") (class "Default")
      (node (ref "R15") (pin "2") (pinfunction "2_2") (pintype "passive"))
      (node (ref "T9") (pin "1") (pintype "passive"))
    )
    (net (code "49") (name "/LS13") (class "Default")
      (node (ref "R16") (pin "2") (pinfunction "2_2") (pintype "passive"))
      (node (ref "T12") (pin "1") (pintype "passive"))
    )
    (net (code "50") (name "/LS14") (class "Default")
      (node (ref "R17") (pin "2") (pinfunction "2_2") (pintype "passive"))
      (node (ref "T15") (pin "1") (pintype "passive"))
    )
    (net (code "51") (name "/LSG0") (class "Default")
      (node (ref "U2") (pin "1") (pinfunction "A0_1") (pintype "passive"))
    )
    (net (code "52") (name "/LSG1") (class "Default")
      (node (ref "U2") (pin "2") (pinfunction "A1_2") (pintype "passive"))
    )
    (net (code "53") (name "/LSG2") (class "Default")
      (node (ref "U2") (pin "3") (pinfunction "A2_3") (pintype "passive"))
    )
    (net (code "56") (name "/SWH0") (class "Default")
      (node (ref "S1") (pin "5") (pinfunction "5_5") (pintype "passive"))
      (node (ref "S2") (pin "5") (pinfunction "5_5") (pintype "passive"))
      (node (ref "S3") (pin "5") (pinfunction "5_5") (pintype "passive"))
      (node (ref "S4") (pin "5") (pinfunction "5_5") (pintype "passive"))
      (node (ref "S5") (pin "5") (pinfunction "5_5") (pintype "passive"))
    )
    (net (code "57") (name "/SWH1") (class "Default")
      (node (ref "S10") (pin "5") (pinfunction "5_5") (pintype "passive"))
      (node (ref "S6") (pin "5") (pinfunction "5_5") (pintype "passive"))
      (node (ref "S7") (pin "5") (pinfunction "5_5") (pintype "passive"))
      (node (ref "S8") (pin "5") (pinfunction "5_5") (pintype "passive"))
      (node (ref "S9") (pin "5") (pinfunction "5_5") (pintype "passive"))
    )
    (net (code "58") (name "/SWH2") (class "Default")
      (node (ref "S11") (pin "5") (pinfunction "5_5") (pintype "passive"))
      (node (ref "S12") (pin "5") (pinfunction "5_5") (pintype "passive"))
      (node (ref "S13") (pin "5") (pinfunction "5_5") (pintype "passive"))
      (node (ref "S14") (pin "5") (pinfunction "5_5") (pintype "passive"))
    )
    (net (code "59") (name "/SWH3") (class "Default")
      (node (ref "S15") (pin "5") (pinfunction "5_5") (pintype "passive"))
      (node (ref "S16") (pin "5") (pinfunction "5_5") (pintype "passive"))
      (node (ref "S17") (pin "5") (pinfunction "5_5") (pintype "passive"))
      (node (ref "S18") (pin "5") (pinfunction "5_5") (pintype "passive"))
      (node (ref "S19") (pin "5") (pinfunction "5_5") (pintype "passive"))
    )
    (net (code "60") (name "/SWH4") (class "Default")
      (node (ref "S20") (pin "5") (pinfunction "5_5") (pintype "passive"))
      (node (ref "S21") (pin "5") (pinfunction "5_5") (pintype "passive"))
      (node (ref "S22") (pin "5") (pinfunction "5_5") (pintype "passive"))
      (node (ref "S23") (pin "5") (pinfunction "5_5") (pintype "passive"))
    )
    (net (code "61") (name "/SWH5") (class "Default")
      (node (ref "S24") (pin "5") (pinfunction "5_5") (pintype "passive"))
      (node (ref "S25") (pin "5") (pinfunction "5_5") (pintype "passive"))
      (node (ref "S26") (pin "5") (pinfunction "5_5") (pintype "passive"))
      (node (ref "S27") (pin "5") (pinfunction "5_5") (pintype "passive"))
    )
    (net (code "63") (name "/SWL0") (class "Default")
      (node (ref "D1") (pin "2") (pintype "passive"))
      (node (ref "D11") (pin "2") (pintype "passive"))
      (node (ref "D15") (pin "2") (pintype "passive"))
      (node (ref "D20") (pin "2") (pintype "passive"))
      (node (ref "D24") (pin "2") (pintype "passive"))
      (node (ref "D6") (pin "2") (pintype "passive"))
    )
    (net (code "64") (name "/SWL1") (class "Default")
      (node (ref "D12") (pin "2") (pintype "passive"))
      (node (ref "D16") (pin "2") (pintype "passive"))
      (node (ref "D2") (pin "2") (pintype "passive"))
      (node (ref "D21") (pin "2") (pintype "passive"))
      (node (ref "D7") (pin "2") (pintype "passive"))
    )
    (net (code "65") (name "/SWL2") (class "Default")
      (node (ref "D13") (pin "2") (pintype "passive"))
      (node (ref "D17") (pin "2") (pintype "passive"))
      (node (ref "D22") (pin "2") (pintype "passive"))
      (node (ref "D25") (pin "2") (pintype "passive"))
      (node (ref "D3") (pin "2") (pintype "passive"))
      (node (ref "D8") (pin "2") (pintype "passive"))
    )
    (net (code "66") (name "/SWL3") (class "Default")
      (node (ref "D14") (pin "2") (pintype "passive"))
      (node (ref "D18") (pin "2") (pintype "passive"))
      (node (ref "D23") (pin "2") (pintype "passive"))
      (node (ref "D26") (pin "2") (pintype "passive"))
      (node (ref "D4") (pin "2") (pintype "passive"))
      (node (ref "D9") (pin "2") (pintype "passive"))
    )
    (net (code "67") (name "/SWL4") (class "Default")
      (node (ref "D10") (pin "2") (pintype "passive"))
      (node (ref "D19") (pin "2") (pintype "passive"))
      (node (ref "D27") (pin "2") (pintype "passive"))
      (node (ref "D5") (pin "2") (pintype "passive"))
    )
    (net (code "71") (name "GND") (class "Default")
      (node (ref "R2") (pin "1") (pinfunction "1_1") (pintype "passive"))
      (node (ref "T17") (pin "2") (pintype "passive"))
      (node (ref "U1") (pin "8") (pinfunction "GND_8") (pintype "passive"))
      (node (ref "U2") (pin "5") (pinfunction "~{E2}_5") (pintype "passive"))
      (node (ref "U2") (pin "8") (pinfunction "GND_8") (pintype "passive"))
      (node (ref "U3") (pin "4") (pinfunction "~{E1}_4") (pintype "passive"))
      (node (ref "U3") (pin "8") (pinfunction "GND_8") (pintype "passive"))
    )
    (net (code "72") (name "Net-(D1-Pad1)") (class "Default")
      (node (ref "D1") (pin "1") (pintype "passive"))
      (node (ref "S1") (pin "6") (pinfunction "6_6") (pintype "passive"))
    )
    (net (code "73") (name "Net-(D2-Pad1)") (class "Default")
      (node (ref "D2") (pin "1") (pintype "passive"))
      (node (ref "S2") (pin "6") (pinfunction "6_6") (pintype "passive"))
    )
    (net (code "74") (name "Net-(D3-Pad1)") (class "Default")
      (node (ref "D3") (pin "1") (pintype "passive"))
      (node (ref "S3") (pin "6") (pinfunction "6_6") (pintype "passive"))
    )
    (net (code "75") (name "Net-(D4-Pad1)") (class "Default")
      (node (ref "D4") (pin "1") (pintype "passive"))
      (node (ref "S4") (pin "6") (pinfunction "6_6") (pintype "passive"))
    )
    (net (code "76") (name "Net-(D5-Pad1)") (class "Default")
      (node (ref "D5") (pin "1") (pintype "passive"))
      (node (ref "S5") (pin "6") (pinfunction "6_6") (pintype "passive"))
    )
    (net (code "77") (name "Net-(D6-Pad1)") (class "Default")
      (node (ref "D6") (pin "1") (pintype "passive"))
      (node (ref "S6") (pin "6") (pinfunction "6_6") (pintype "passive"))
    )
    (net (code "78") (name "Net-(D7-Pad1)") (class "Default")
      (node (ref "D7") (pin "1") (pintype "passive"))
      (node (ref "S7") (pin "6") (pinfunction "6_6") (pintype "passive"))
    )
    (net (code "79") (name "Net-(D8-Pad1)") (class "Default")
      (node (ref "D8") (pin "1") (pintype "passive"))
      (node (ref "S8") (pin "6") (pinfunction "6_6") (pintype "passive"))
    )
    (net (code "80") (name "Net-(D9-Pad1)") (class "Default")
      (node (ref "D9") (pin "1") (pintype "passive"))
      (node (ref "S9") (pin "6") (pinfunction "6_6") (pintype "passive"))
    )
    (net (code "81") (name "Net-(D10-Pad1)") (class "Default")
      (node (ref "D10") (pin "1") (pintype "passive"))
      (node (ref "S10") (pin "6") (pinfunction "6_6") (pintype "passive"))
    )
    (net (code "82") (name "Net-(D11-Pad1)") (class "Default")
      (node (ref "D11") (pin "1") (pintype "passive"))
      (node (ref "S11") (pin "6") (pinfunction "6_6") (pintype "passive"))
    )
    (net (code "83") (name "Net-(D12-Pad1)") (class "Default")
      (node (ref "D12") (pin "1") (pintype "passive"))
      (node (ref "S12") (pin "6") (pinfunction "6_6") (pintype "passive"))
    )
    (net (code "84") (name "Net-(D13-Pad1)") (class "Default")
      (node (ref "D13") (pin "1") (pintype "passive"))
      (node (ref "S13") (pin "6") (pinfunction "6_6") (pintype "passive"))
    )
    (net (code "85") (name "Net-(D14-Pad1)") (class "Default")
      (node (ref "D14") (pin "1") (pintype "passive"))
      (node (ref "S14") (pin "6") (pinfunction "6_6") (pintype "passive"))
    )
    (net (code "86") (name "Net-(D15-Pad1)") (class "Default")
      (node (ref "D15") (pin "1") (pintype "passive"))
      (node (ref "S15") (pin "6") (pinfunction "6_6") (pintype "passive"))
    )
    (net (code "87") (name "Net-(D16-Pad1)") (class "Default")
      (node (ref "D16") (pin "1") (pintype "passive"))
      (node (ref "S16") (pin "6") (pinfunction "6_6") (pintype "passive"))
    )
    (net (code "88") (name "Net-(D17-Pad1)") (class "Default")
      (node (ref "D17") (pin "1") (pintype "passive"))
      (node (ref "S17") (pin "6") (pinfunction "6_6") (pintype "passive"))
    )
    (net (code "89") (name "Net-(D18-Pad1)") (class "Default")
      (node (ref "D18") (pin "1") (pintype "passive"))
      (node (ref "S18") (pin "6") (pinfunction "6_6") (pintype "passive"))
    )
    (net (code "90") (name "Net-(D19-Pad1)") (class "Default")
      (node (ref "D19") (pin "1") (pintype "passive"))
      (node (ref "S19") (pin "6") (pinfunction "6_6") (pintype "passive"))
    )
    (net (code "91") (name "Net-(D20-Pad1)") (class "Default")
      (node (ref "D20") (pin "1") (pintype "passive"))
      (node (ref "S20") (pin "6") (pinfunction "6_6") (pintype "passive"))
    )
    (net (code "92") (name "Net-(D21-Pad1)") (class "Default")
      (node (ref "D21") (pin "1") (pintype "passive"))
      (node (ref "S21") (pin "6") (pinfunction "6_6") (pintype "passive"))
    )
    (net (code "93") (name "Net-(D22-Pad1)") (class "Default")
      (node (ref "D22") (pin "1") (pintype "passive"))
      (node (ref "S22") (pin "6") (pinfunction "6_6") (pintype "passive"))
    )
    (net (code "94") (name "Net-(D23-Pad1)") (class "Default")
      (node (ref "D23") (pin "1") (pintype "passive"))
      (node (ref "S23") (pin "6") (pinfunction "6_6") (pintype "passive"))
    )
    (net (code "95") (name "Net-(D24-Pad1)") (class "Default")
      (node (ref "D24") (pin "1") (pintype "passive"))
      (node (ref "S24") (pin "6") (pinfunction "6_6") (pintype "passive"))
    )
    (net (code "96") (name "Net-(D25-Pad1)") (class "Default")
      (node (ref "D25") (pin "1") (pintype "passive"))
      (node (ref "S25") (pin "6") (pinfunction "6_6") (pintype "passive"))
    )
    (net (code "97") (name "Net-(D26-Pad1)") (class "Default")
      (node (ref "D26") (pin "1") (pintype "passive"))
      (node (ref "S26") (pin "6") (pinfunction "6_6") (pintype "passive"))
    )
    (net (code "98") (name "Net-(D27-Pad1)") (class "Default")
      (node (ref "D27") (pin "1") (pintype "passive"))
      (node (ref "S27") (pin "6") (pinfunction "6_6") (pintype "passive"))
    )
    (net (code "99") (name "Net-(R1-Pad1)") (class "Default")
      (node (ref "R1") (pin "1") (pinfunction "1_1") (pintype "passive"))
      (node (ref "T16") (pin "1") (pintype "passive"))
      (node (ref "T17") (pin "3") (pintype "passive"))
    )
    (net (code "100") (name "Net-(R2-Pad2)") (class "Default")
      (node (ref "R2") (pin "2") (pinfunction "2_2") (pintype "passive"))
      (node (ref "T16") (pin "2") (pintype "passive"))
      (node (ref "T17") (pin "1") (pintype "passive"))
    )
    (net (code "101") (name "Net-(T1-Pad2)") (class "Default")
      (node (ref "T1") (pin "2") (pintype "passive"))
      (node (ref "T10") (pin "2") (pintype "passive"))
      (node (ref "T11") (pin "2") (pintype "passive"))
      (node (ref "T12") (pin "2") (pintype "passive"))
      (node (ref "T13") (pin "2") (pintype "passive"))
      (node (ref "T14") (pin "2") (pintype "passive"))
      (node (ref "T15") (pin "2") (pintype "passive"))
      (node (ref "T16") (pin "3") (pintype "passive"))
      (node (ref "T2") (pin "2") (pintype "passive"))
      (node (ref "T3") (pin "2") (pintype "passive"))
      (node (ref "T4") (pin "2") (pintype "passive"))
      (node (ref "T5") (pin "2") (pintype "passive"))
      (node (ref "T6") (pin "2") (pintype "passive"))
      (node (ref "T7") (pin "2") (pintype "passive"))
      (node (ref "T8") (pin "2") (pintype "passive"))
      (node (ref "T9") (pin "2") (pintype "passive"))
    )
    (net (code "102") (name "Net-(U1-Y0)") (class "Default")
      (node (ref "R3") (pin "1") (pinfunction "1_1") (pintype "passive"))
      (node (ref "U1") (pin "15") (pinfunction "Y0_15") (pintype "passive"))
    )
    (net (code "103") (name "Net-(U1-Y1)") (class "Default")
      (node (ref "R4") (pin "1") (pinfunction "1_1") (pintype "passive"))
      (node (ref "U1") (pin "14") (pinfunction "Y1_14") (pintype "passive"))
    )
    (net (code "104") (name "Net-(U1-Y2)") (class "Default")
      (node (ref "R5") (pin "1") (pinfunction "1_1") (pintype "passive"))
      (node (ref "U1") (pin "13") (pinfunction "Y2_13") (pintype "passive"))
    )
    (net (code "105") (name "Net-(U1-Y3)") (class "Default")
      (node (ref "R6") (pin "1") (pinfunction "1_1") (pintype "passive"))
      (node (ref "U1") (pin "12") (pinfunction "Y3_12") (pintype "passive"))
    )
    (net (code "106") (name "Net-(U1-Y4)") (class "Default")
      (node (ref "R7") (pin "1") (pinfunction "1_1") (pintype "passive"))
      (node (ref "U1") (pin "11") (pinfunction "Y4_11") (pintype "passive"))
    )
    (net (code "107") (name "Net-(U1-Y5)") (class "Default")
      (node (ref "R9") (pin "1") (pinfunction "1_1") (pintype "passive"))
      (node (ref "U1") (pin "10") (pinfunction "Y5_10") (pintype "passive"))
    )
    (net (code "108") (name "Net-(U1-Y6)") (class "Default")
      (node (ref "R10") (pin "1") (pinfunction "1_1") (pintype "passive"))
      (node (ref "U1") (pin "9") (pinfunction "Y6_9") (pintype "passive"))
    )
    (net (code "109") (name "Net-(U1-Y7)") (class "Default")
      (node (ref "R8") (pin "2") (pinfunction "2_2") (pintype "passive"))
      (node (ref "U1") (pin "7") (pinfunction "Y7_7") (pintype "passive"))
    )
    (net (code "110") (name "Net-(U2-~{Y0})") (class "Default")
      (node (ref "R18") (pin "1") (pinfunction "1_1") (pintype "passive"))
      (node (ref "U2") (pin "15") (pinfunction "~{Y0}_15") (pintype "passive"))
    )
    (net (code "111") (name "Net-(U2-~{Y1})") (class "Default")
      (node (ref "R19") (pin "1") (pinfunction "1_1") (pintype "passive"))
      (node (ref "U2") (pin "14") (pinfunction "~{Y1}_14") (pintype "passive"))
    )
    (net (code "112") (name "Net-(U2-~{Y2})") (class "Default")
      (node (ref "R20") (pin "1") (pinfunction "1_1") (pintype "passive"))
      (node (ref "U2") (pin "13") (pinfunction "~{Y2}_13") (pintype "passive"))
    )
    (net (code "113") (name "Net-(U2-~{Y3})") (class "Default")
      (node (ref "R21") (pin "1") (pinfunction "1_1") (pintype "passive"))
      (node (ref "U2") (pin "12") (pinfunction "~{Y3}_12") (pintype "passive"))
    )
    (net (code "114") (name "Net-(U2-~{Y4})") (class "Default")
      (node (ref "R22") (pin "1") (pinfunction "1_1") (pintype "passive"))
      (node (ref "U2") (pin "11") (pinfunction "~{Y4}_11") (pintype "passive"))
    )
    (net (code "115") (name "Net-(U2-~{Y5})") (class "Default")
      (node (ref "R23") (pin "1") (pinfunction "1_1") (pintype "passive"))
      (node (ref "U2") (pin "10") (pinfunction "~{Y5}_10") (pintype "passive"))
    )
    (net (code "116") (name "Net-(U3-Y0)") (class "Default")
      (node (ref "R11") (pin "1") (pinfunction "1_1") (pintype "passive"))
      (node (ref "U3") (pin "15") (pinfunction "Y0_15") (pintype "passive"))
    )
    (net (code "117") (name "Net-(U3-Y1)") (class "Default")
      (node (ref "R12") (pin "1") (pinfunction "1_1") (pintype "passive"))
      (node (ref "U3") (pin "14") (pinfunction "Y1_14") (pintype "passive"))
    )
    (net (code "118") (name "Net-(U3-Y2)") (class "Default")
      (node (ref "R13") (pin "1") (pinfunction "1_1") (pintype "passive"))
      (node (ref "U3") (pin "13") (pinfunction "Y2_13") (pintype "passive"))
    )
    (net (code "119") (name "Net-(U3-Y3)") (class "Default")
      (node (ref "R14") (pin "1") (pinfunction "1_1") (pintype "passive"))
      (node (ref "U3") (pin "12") (pinfunction "Y3_12") (pintype "passive"))
    )
    (net (code "120") (name "Net-(U3-Y4)") (class "Default")
      (node (ref "R15") (pin "1") (pinfunction "1_1") (pintype "passive"))
      (node (ref "U3") (pin "11") (pinfunction "Y4_11") (pintype "passive"))
    )
    (net (code "121") (name "Net-(U3-Y5)") (class "Default")
      (node (ref "R16") (pin "1") (pinfunction "1_1") (pintype "passive"))
      (node (ref "U3") (pin "10") (pinfunction "Y5_10") (pintype "passive"))
    )
    (net (code "122") (name "Net-(U3-Y6)") (class "Default")
      (node (ref "R17") (pin "1") (pinfunction "1_1") (pintype "passive"))
      (node (ref "U3") (pin "9") (pinfunction "Y6_9") (pintype "passive"))
    )
    (net (code "123") (name "unconnected-(U2-~{Y6}-Pad9)") (class "Default")
      (node (ref "U2") (pin "9") (pinfunction "~{Y6}_9") (pintype "passive+no_connect"))
    )
    (net (code "124") (name "unconnected-(U2-~{Y7}-Pad7)") (class "Default")
      (node (ref "U2") (pin "7") (pinfunction "~{Y7}_7") (pintype "passive+no_connect"))
    )
    (net (code "125") (name "unconnected-(U3-Y7-Pad7)") (class "Default")
      (node (ref "U3") (pin "7") (pinfunction "Y7_7") (pintype "passive+no_connect"))
    )
  )
)
